# STM32Debuuger.net
KiCad netlist of a schematic drawn in Altium Designer
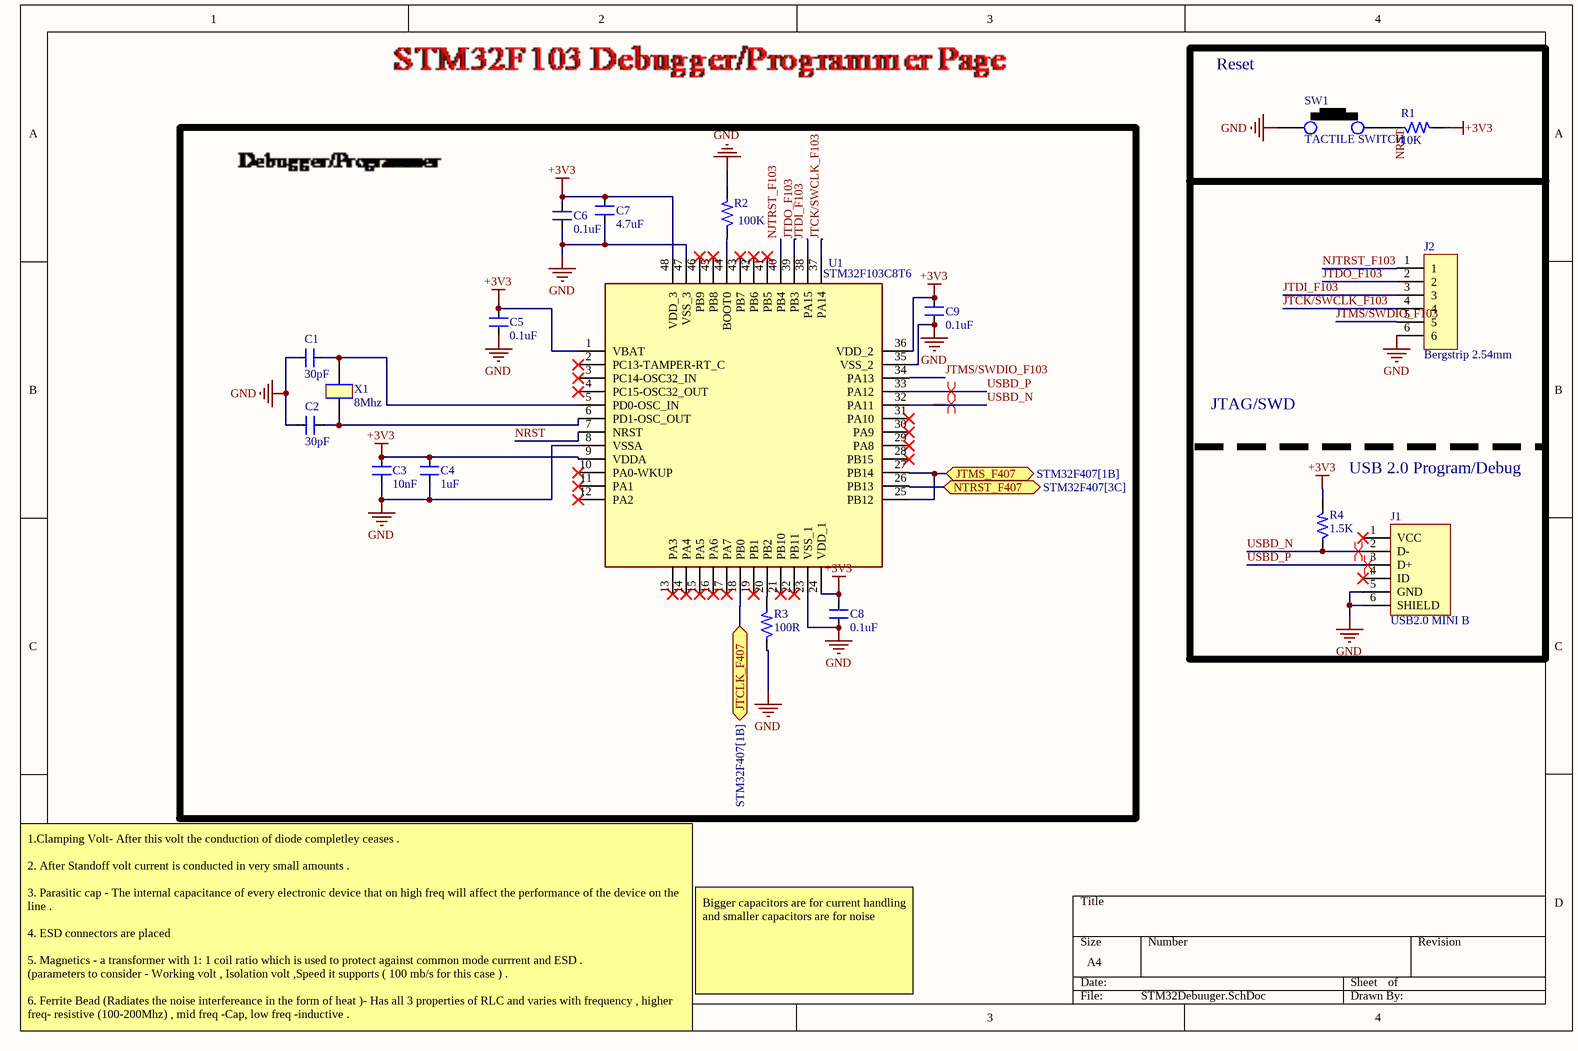
[diagram p0: STM32Debuuger.SchDoc]

(export (version "E")
  (design (tool "Eeschema 10.0.6"))
  (components
    (comp (ref "C1")
      (value "30pF")
      (footprint "CAP_0805")
      (description "±10% 50V Ceramic Capacitor C0G, NP0 0805 (2012 Metric)")
      (fields
        (field (name "MANUFACTURER PART NUMBER") "C0805C300K5GAC7800")
        (field (name "MANUFACTURER") "KEMET")
      )
      (libsource (lib "ESTEEMPCBLIB") (part "CAP_30pF-50V-10%-0805"))
    )
    (comp (ref "C2")
      (value "30pF")
      (footprint "CAP_0805")
      (description "±10% 50V Ceramic Capacitor C0G, NP0 0805 (2012 Metric)")
      (fields
        (field (name "MANUFACTURER PART NUMBER") "C0805C300K5GAC7800")
        (field (name "MANUFACTURER") "KEMET")
      )
      (libsource (lib "ESTEEMPCBLIB") (part "CAP_30pF-50V-10%-0805"))
    )
    (comp (ref "C3")
      (value "10nF")
      (footprint "CAP_0805")
      (description "10000pF ±10% 50V Ceramic Capacitor X7R 0805 (2012 Metric)")
      (fields
        (field (name "MANUFACTURER") "Samsung")
        (field (name "MANUFACTURER PART NUMBER") "C0805C103K5RECAUTO")
      )
      (libsource (lib "ESTEEMPCBLIB") (part "CAP_10nF-50V-10%-0805"))
    )
    (comp (ref "C4")
      (value "1uF")
      (footprint "CAP_0805")
      (description "1µF ±5% 50V Ceramic Capacitor X7R 0805 (2012 Metric)")
      (fields
        (field (name "MANUFACTURER") "Samsung")
        (field (name "MANUFACTURER PART NUMBER") "CC0805JKX7R9BB105")
      )
      (libsource (lib "ESTEEMPCBLIB") (part "CAP_1uF-50V-5%-0805"))
    )
    (comp (ref "C5")
      (value "0.1uF")
      (footprint "CAP_0805")
      (description "0.1µF ±10% 50V Ceramic Capacitor X7R 0805 (2012 Metric)")
      (fields
        (field (name "MANUFACTURER") "Samsung")
        (field (name "MANUFACTURER PART NUMBER") "CL21B104KBCNNNC")
      )
      (libsource (lib "ESTEEMPCBLIB") (part "CAP_0.1uF-50V-10%-0805"))
    )
    (comp (ref "C6")
      (value "0.1uF")
      (footprint "CAP_0805")
      (description "0.1µF ±10% 50V Ceramic Capacitor X7R 0805 (2012 Metric)")
      (fields
        (field (name "MANUFACTURER") "Samsung")
        (field (name "MANUFACTURER PART NUMBER") "CL21B104KBCNNNC")
      )
      (libsource (lib "ESTEEMPCBLIB") (part "CAP_0.1uF-50V-10%-0805"))
    )
    (comp (ref "C7")
      (value "4.7uF")
      (footprint "CAP_0805")
      (description "4.7µF ±10% 50V Ceramic Capacitor X5R 0805 (2012 Metric)")
      (fields
        (field (name "MANUFACTURER") "Yageo")
        (field (name "MANUFACTURER PART NUMBER") "GRM21BR61H475KE51L")
      )
      (libsource (lib "ESTEEMPCBLIB") (part "CAP_4.7uF-50V-10%-0805"))
    )
    (comp (ref "C8")
      (value "0.1uF")
      (footprint "CAP_0805")
      (description "0.1µF ±10% 50V Ceramic Capacitor X7R 0805 (2012 Metric)")
      (fields
        (field (name "MANUFACTURER") "Samsung")
        (field (name "MANUFACTURER PART NUMBER") "CL21B104KBCNNNC")
      )
      (libsource (lib "ESTEEMPCBLIB") (part "CAP_0.1uF-50V-10%-0805"))
    )
    (comp (ref "C9")
      (value "0.1uF")
      (footprint "CAP_0805")
      (description "0.1µF ±10% 50V Ceramic Capacitor X7R 0805 (2012 Metric)")
      (fields
        (field (name "MANUFACTURER") "Samsung")
        (field (name "MANUFACTURER PART NUMBER") "CL21B104KBCNNNC")
      )
      (libsource (lib "ESTEEMPCBLIB") (part "CAP_0.1uF-50V-10%-0805"))
    )
    (comp (ref "J1")
      (value "USB2.0 MINI B")
      (footprint "CON_690-005-299-043")
      (description "USB - mini B USB 2.0 Receptacle Connector 5 Position Surface Mount, Right Angle")
      (fields
        (field (name "MANUFACTURER") "EDAC")
        (field (name "MANUFACTURER PART NUMBER") "690-005-299-043")
      )
      (libsource (lib "ESTEEMPCBLIB") (part "CON_USB2.0-MINIB-SMD"))
    )
    (comp (ref "J2")
      (value "Bergstrip 2.54mm")
      (footprint "CON6_100_59D78_TH_ST")
      (description "6 Pins, 1 Row 2.54mm Pitch, Straight bergstrip, Female")
      (fields (field (name "MANUFACTURER") "Molex") (field (name "MANUFACTURER PART NUMBER") "22-10-2061"))
      (libsource (lib "ESTEEMPCBLIB") (part "CON-BS-SKT_6X1-100-ST-TH"))
    )
    (comp (ref "R1")
      (value "10K")
      (footprint "RES_0603")
      (description "10 kOhms ±1% 0.1W, 1/10W Chip Resistor 0603 (1608 Metric) Automotive AEC-Q200 Thick Film")
      (fields (field (name "MANUFACTURER") "Walsin") (field (name "MANUFACTURER PART NUMBER") "WR06X1002FTL"))
      (libsource (lib "ESTEEMPCBLIB") (part "RES_10K-0.1W-1%-0603"))
    )
    (comp (ref "R2")
      (value "100K")
      (footprint "RES_0805")
      (description "100 kOhms ±1% 0.125W, 1/8W Chip Resistor 0805 (2012 Metric) Automotive AEC-Q200 Thick Film")
      (fields (field (name "MANUFACTURER") "Walsin") (field (name "MANUFACTURER PART NUMBER") "WR08X1003FTL"))
      (libsource (lib "ESTEEMPCBLIB") (part "RES_100K-0.125W-1%-0805"))
    )
    (comp (ref "R3")
      (value "100R")
      (footprint "RES_0603")
      (description "100 Ohms ±1% 0.1W, 1/10W Chip Resistor 0603 (1608 Metric) Thick Film")
      (fields (field (name "MANUFACTURER") "Walsin") (field (name "MANUFACTURER PART NUMBER") "WR06X1000FTL"))
      (libsource (lib "ESTEEMPCBLIB") (part "RES_100R-0.1W-1%-0603"))
    )
    (comp (ref "R4")
      (value "1.5K")
      (footprint "RES_0805")
      (description "1.5 kOhms ±1% 0.125W, 1/8W Chip Resistor 0805 (2012 Metric) Thick Film")
      (fields
        (field (name "MANUFACTURER") "TE Connectivity Passive Product")
        (field (name "MANUFACTURER PART NUMBER") "CRG0805F1K5")
      )
      (libsource (lib "ESTEEMPCBLIB") (part "RES_1.5K-0.125W-1%-0805"))
    )
    (comp (ref "SW1")
      (value "TACTILE SWITCH")
      (footprint "SW_342_SMD")
      (description "Tactile Switch SPST-NO Top Actuated Surface Mount")
      (fields
        (field (name "MANUFACTURER") "ITT C&K")
        (field (name "MANUFACTURER PART NUMBER") "RS-282G05A3-SMRT")
      )
      (libsource (lib "ESTEEMPCBLIB") (part "SW1_RS-282G05A3-SMRT-SMD"))
    )
    (comp (ref "U1")
      (value "STM32F103C8T6")
      (footprint "LQFP-48_19.6_393_58X11_SMD")
      (description "ARM® Cortex®-M3 STM32F1 Microcontroller IC 32-Bit 72MHz 64KB (64K x 8) FLASH 48-LQFP (7x7)")
      (fields (field (name "MANUFACTURER") "STMicroelectronics"))
      (libsource (lib "ESTEEMPCBLIB") (part "IC_STM32F103C8T6"))
    )
    (comp (ref "X1")
      (value "8Mhz")
      (footprint "XTAL_314_240X47_SMD")
      (description "8MHz ±30ppm Crystal 32pF 60 Ohms HC-49/US")
      (fields
        (field (name "MANUFACTURER") "Fox Electronics")
        (field (name "MANUFACTURER PART NUMBER") "ECS-80-32-5PX-TR")
      )
      (libsource (lib "ESTEEMPCBLIB") (part "XTAL_8MHZ-ECS-80-32-5PX-SMD"))
    )
  )
  (nets
    (net (code "1") (name "+3V3") (class "Default")
      (node (ref "C3") (pin "2") (pinfunction "2_2") (pintype "passive"))
      (node (ref "C4") (pin "2") (pinfunction "2_2") (pintype "passive"))
      (node (ref "C5") (pin "2") (pinfunction "2_2") (pintype "passive"))
      (node (ref "C6") (pin "2") (pinfunction "2_2") (pintype "passive"))
      (node (ref "C7") (pin "2") (pinfunction "2_2") (pintype "passive"))
      (node (ref "C8") (pin "2") (pinfunction "2_2") (pintype "passive"))
      (node (ref "C9") (pin "2") (pinfunction "2_2") (pintype "passive"))
      (node (ref "R1") (pin "2") (pinfunction "2_2") (pintype "passive"))
      (node (ref "R4") (pin "2") (pinfunction "2_2") (pintype "passive"))
      (node (ref "U1") (pin "1") (pinfunction "VBAT_1") (pintype "passive"))
      (node (ref "U1") (pin "24") (pinfunction "VDD_1_24") (pintype "passive"))
      (node (ref "U1") (pin "36") (pinfunction "VDD_2_36") (pintype "passive"))
      (node (ref "U1") (pin "48") (pinfunction "VDD_3_48") (pintype "passive"))
      (node (ref "U1") (pin "9") (pinfunction "VDDA_9") (pintype "passive"))
    )
    (net (code "2") (name "/JTCK{slash}SWCLK_F103") (class "Default")
      (node (ref "J2") (pin "4") (pinfunction "4_4") (pintype "passive"))
      (node (ref "U1") (pin "37") (pinfunction "PA14_37") (pintype "passive"))
    )
    (net (code "3") (name "/JTCLK_F407") (class "Default")
      (node (ref "U1") (pin "18") (pinfunction "PB0_18") (pintype "passive"))
    )
    (net (code "4") (name "/JTDI_F103") (class "Default")
      (node (ref "J2") (pin "3") (pinfunction "3_3") (pintype "passive"))
      (node (ref "U1") (pin "38") (pinfunction "PA15_38") (pintype "passive"))
    )
    (net (code "5") (name "/JTDO_F103") (class "Default")
      (node (ref "J2") (pin "2") (pinfunction "2_2") (pintype "passive"))
      (node (ref "U1") (pin "39") (pinfunction "PB3_39") (pintype "passive"))
    )
    (net (code "6") (name "/JTMS_F407") (class "Default")
      (node (ref "U1") (pin "25") (pinfunction "PB12_25") (pintype "passive"))
      (node (ref "U1") (pin "27") (pinfunction "PB14_27") (pintype "passive"))
    )
    (net (code "7") (name "/JTMS{slash}SWDIO_F103") (class "Default")
      (node (ref "J2") (pin "5") (pinfunction "5_5") (pintype "passive"))
      (node (ref "U1") (pin "34") (pinfunction "PA13_34") (pintype "passive"))
    )
    (net (code "8") (name "/NJTRST_F103") (class "Default")
      (node (ref "J2") (pin "1") (pinfunction "1_1") (pintype "passive"))
      (node (ref "U1") (pin "40") (pinfunction "PB4_40") (pintype "passive"))
    )
    (net (code "9") (name "/NRST") (class "Default")
      (node (ref "R1") (pin "1") (pinfunction "1_1") (pintype "passive"))
      (node (ref "SW1") (pin "2") (pinfunction "2_2") (pintype "passive"))
      (node (ref "U1") (pin "7") (pinfunction "NRST_7") (pintype "passive"))
    )
    (net (code "10") (name "/NTRST_F407") (class "Default")
      (node (ref "U1") (pin "26") (pinfunction "PB13_26") (pintype "passive"))
    )
    (net (code "11") (name "/USBD_N") (class "Default")
      (node (ref "J1") (pin "2") (pinfunction "D-_2") (pintype "passive"))
      (node (ref "R4") (pin "1") (pinfunction "1_1") (pintype "passive"))
      (node (ref "U1") (pin "32") (pinfunction "PA11_32") (pintype "passive"))
    )
    (net (code "12") (name "/USBD_P") (class "Default")
      (node (ref "J1") (pin "3") (pinfunction "D+_3") (pintype "passive"))
      (node (ref "U1") (pin "33") (pinfunction "PA12_33") (pintype "passive"))
    )
    (net (code "13") (name "GND") (class "Default")
      (node (ref "C1") (pin "1") (pinfunction "1_1") (pintype "passive"))
      (node (ref "C2") (pin "1") (pinfunction "1_1") (pintype "passive"))
      (node (ref "C3") (pin "1") (pinfunction "1_1") (pintype "passive"))
      (node (ref "C4") (pin "1") (pinfunction "1_1") (pintype "passive"))
      (node (ref "C5") (pin "1") (pinfunction "1_1") (pintype "passive"))
      (node (ref "C6") (pin "1") (pinfunction "1_1") (pintype "passive"))
      (node (ref "C7") (pin "1") (pinfunction "1_1") (pintype "passive"))
      (node (ref "C8") (pin "1") (pinfunction "1_1") (pintype "passive"))
      (node (ref "C9") (pin "1") (pinfunction "1_1") (pintype "passive"))
      (node (ref "J1") (pin "5") (pinfunction "GND_5") (pintype "passive"))
      (node (ref "J1") (pin "6") (pinfunction "SHIELD_6") (pintype "passive"))
      (node (ref "J2") (pin "6") (pinfunction "6_6") (pintype "passive"))
      (node (ref "R2") (pin "2") (pinfunction "2_2") (pintype "passive"))
      (node (ref "R3") (pin "1") (pinfunction "1_1") (pintype "passive"))
      (node (ref "SW1") (pin "1") (pinfunction "1_1") (pintype "passive"))
      (node (ref "U1") (pin "23") (pinfunction "VSS_1_23") (pintype "passive"))
      (node (ref "U1") (pin "35") (pinfunction "VSS_2_35") (pintype "passive"))
      (node (ref "U1") (pin "47") (pinfunction "VSS_3_47") (pintype "passive"))
      (node (ref "U1") (pin "8") (pinfunction "VSSA_8") (pintype "passive"))
    )
    (net (code "14") (name "Net-(U1-BOOT0)") (class "Default")
      (node (ref "R2") (pin "1") (pinfunction "1_1") (pintype "passive"))
      (node (ref "U1") (pin "44") (pinfunction "BOOT0_44") (pintype "passive"))
    )
    (net (code "15") (name "Net-(U1-PB2)") (class "Default")
      (node (ref "R3") (pin "2") (pinfunction "2_2") (pintype "passive"))
      (node (ref "U1") (pin "20") (pinfunction "PB2_20") (pintype "passive"))
    )
    (net (code "16") (name "Net-(U1-PD0-OSC_IN)") (class "Default")
      (node (ref "C1") (pin "2") (pinfunction "2_2") (pintype "passive"))
      (node (ref "U1") (pin "5") (pinfunction "PD0-OSC_IN_5") (pintype "passive"))
      (node (ref "X1") (pin "2") (pinfunction "2_2") (pintype "passive"))
    )
    (net (code "17") (name "Net-(U1-PD1-OSC_OUT)") (class "Default")
      (node (ref "C2") (pin "2") (pinfunction "2_2") (pintype "passive"))
      (node (ref "U1") (pin "6") (pinfunction "PD1-OSC_OUT_6") (pintype "passive"))
      (node (ref "X1") (pin "1") (pinfunction "1_1") (pintype "passive"))
    )
    (net (code "18") (name "unconnected-(J1-ID-Pad4)") (class "Default")
      (node (ref "J1") (pin "4") (pinfunction "ID_4") (pintype "passive+no_connect"))
    )
    (net (code "19") (name "unconnected-(J1-VCC-Pad1)") (class "Default")
      (node (ref "J1") (pin "1") (pinfunction "VCC_1") (pintype "passive+no_connect"))
    )
    (net (code "20") (name "unconnected-(U1-PA0-WKUP-Pad10)") (class "Default")
      (node (ref "U1") (pin "10") (pinfunction "PA0-WKUP_10") (pintype "passive+no_connect"))
    )
    (net (code "21") (name "unconnected-(U1-PA1-Pad11)") (class "Default")
      (node (ref "U1") (pin "11") (pinfunction "PA1_11") (pintype "passive+no_connect"))
    )
    (net (code "22") (name "unconnected-(U1-PA2-Pad12)") (class "Default")
      (node (ref "U1") (pin "12") (pinfunction "PA2_12") (pintype "passive+no_connect"))
    )
    (net (code "23") (name "unconnected-(U1-PA3-Pad13)") (class "Default")
      (node (ref "U1") (pin "13") (pinfunction "PA3_13") (pintype "passive+no_connect"))
    )
    (net (code "24") (name "unconnected-(U1-PA4-Pad14)") (class "Default")
      (node (ref "U1") (pin "14") (pinfunction "PA4_14") (pintype "passive+no_connect"))
    )
    (net (code "25") (name "unconnected-(U1-PA5-Pad15)") (class "Default")
      (node (ref "U1") (pin "15") (pinfunction "PA5_15") (pintype "passive+no_connect"))
    )
    (net (code "26") (name "unconnected-(U1-PA6-Pad16)") (class "Default")
      (node (ref "U1") (pin "16") (pinfunction "PA6_16") (pintype "passive+no_connect"))
    )
    (net (code "27") (name "unconnected-(U1-PA7-Pad17)") (class "Default")
      (node (ref "U1") (pin "17") (pinfunction "PA7_17") (pintype "passive+no_connect"))
    )
    (net (code "28") (name "unconnected-(U1-PA8-Pad29)") (class "Default")
      (node (ref "U1") (pin "29") (pinfunction "PA8_29") (pintype "passive+no_connect"))
    )
    (net (code "29") (name "unconnected-(U1-PA9-Pad30)") (class "Default")
      (node (ref "U1") (pin "30") (pinfunction "PA9_30") (pintype "passive+no_connect"))
    )
    (net (code "30") (name "unconnected-(U1-PA10-Pad31)") (class "Default")
      (node (ref "U1") (pin "31") (pinfunction "PA10_31") (pintype "passive+no_connect"))
    )
    (net (code "31") (name "unconnected-(U1-PB1-Pad19)") (class "Default")
      (node (ref "U1") (pin "19") (pinfunction "PB1_19") (pintype "passive+no_connect"))
    )
    (net (code "32") (name "unconnected-(U1-PB5-Pad41)") (class "Default")
      (node (ref "U1") (pin "41") (pinfunction "PB5_41") (pintype "passive+no_connect"))
    )
    (net (code "33") (name "unconnected-(U1-PB6-Pad42)") (class "Default")
      (node (ref "U1") (pin "42") (pinfunction "PB6_42") (pintype "passive+no_connect"))
    )
    (net (code "34") (name "unconnected-(U1-PB7-Pad43)") (class "Default")
      (node (ref "U1") (pin "43") (pinfunction "PB7_43") (pintype "passive+no_connect"))
    )
    (net (code "35") (name "unconnected-(U1-PB8-Pad45)") (class "Default")
      (node (ref "U1") (pin "45") (pinfunction "PB8_45") (pintype "passive+no_connect"))
    )
    (net (code "36") (name "unconnected-(U1-PB9-Pad46)") (class "Default")
      (node (ref "U1") (pin "46") (pinfunction "PB9_46") (pintype "passive+no_connect"))
    )
    (net (code "37") (name "unconnected-(U1-PB10-Pad21)") (class "Default")
      (node (ref "U1") (pin "21") (pinfunction "PB10_21") (pintype "passive+no_connect"))
    )
    (net (code "38") (name "unconnected-(U1-PB11-Pad22)") (class "Default")
      (node (ref "U1") (pin "22") (pinfunction "PB11_22") (pintype "passive+no_connect"))
    )
    (net (code "39") (name "unconnected-(U1-PB15-Pad28)") (class "Default")
      (node (ref "U1") (pin "28") (pinfunction "PB15_28") (pintype "passive+no_connect"))
    )
    (net (code "40") (name "unconnected-(U1-PC13-TAMPER-RT_C-Pad2)") (class "Default")
      (node (ref "U1") (pin "2") (pinfunction "PC13-TAMPER-RT_C_2") (pintype "passive+no_connect"))
    )
    (net (code "41") (name "unconnected-(U1-PC14-OSC32_IN-Pad3)") (class "Default")
      (node (ref "U1") (pin "3") (pinfunction "PC14-OSC32_IN_3") (pintype "passive+no_connect"))
    )
    (net (code "42") (name "unconnected-(U1-PC15-OSC32_OUT-Pad4)") (class "Default")
      (node (ref "U1") (pin "4") (pinfunction "PC15-OSC32_OUT_4") (pintype "passive+no_connect"))
    )
  )
)
